# PCB_esp32.net
KiCad netlist of a schematic drawn in Altium Designer
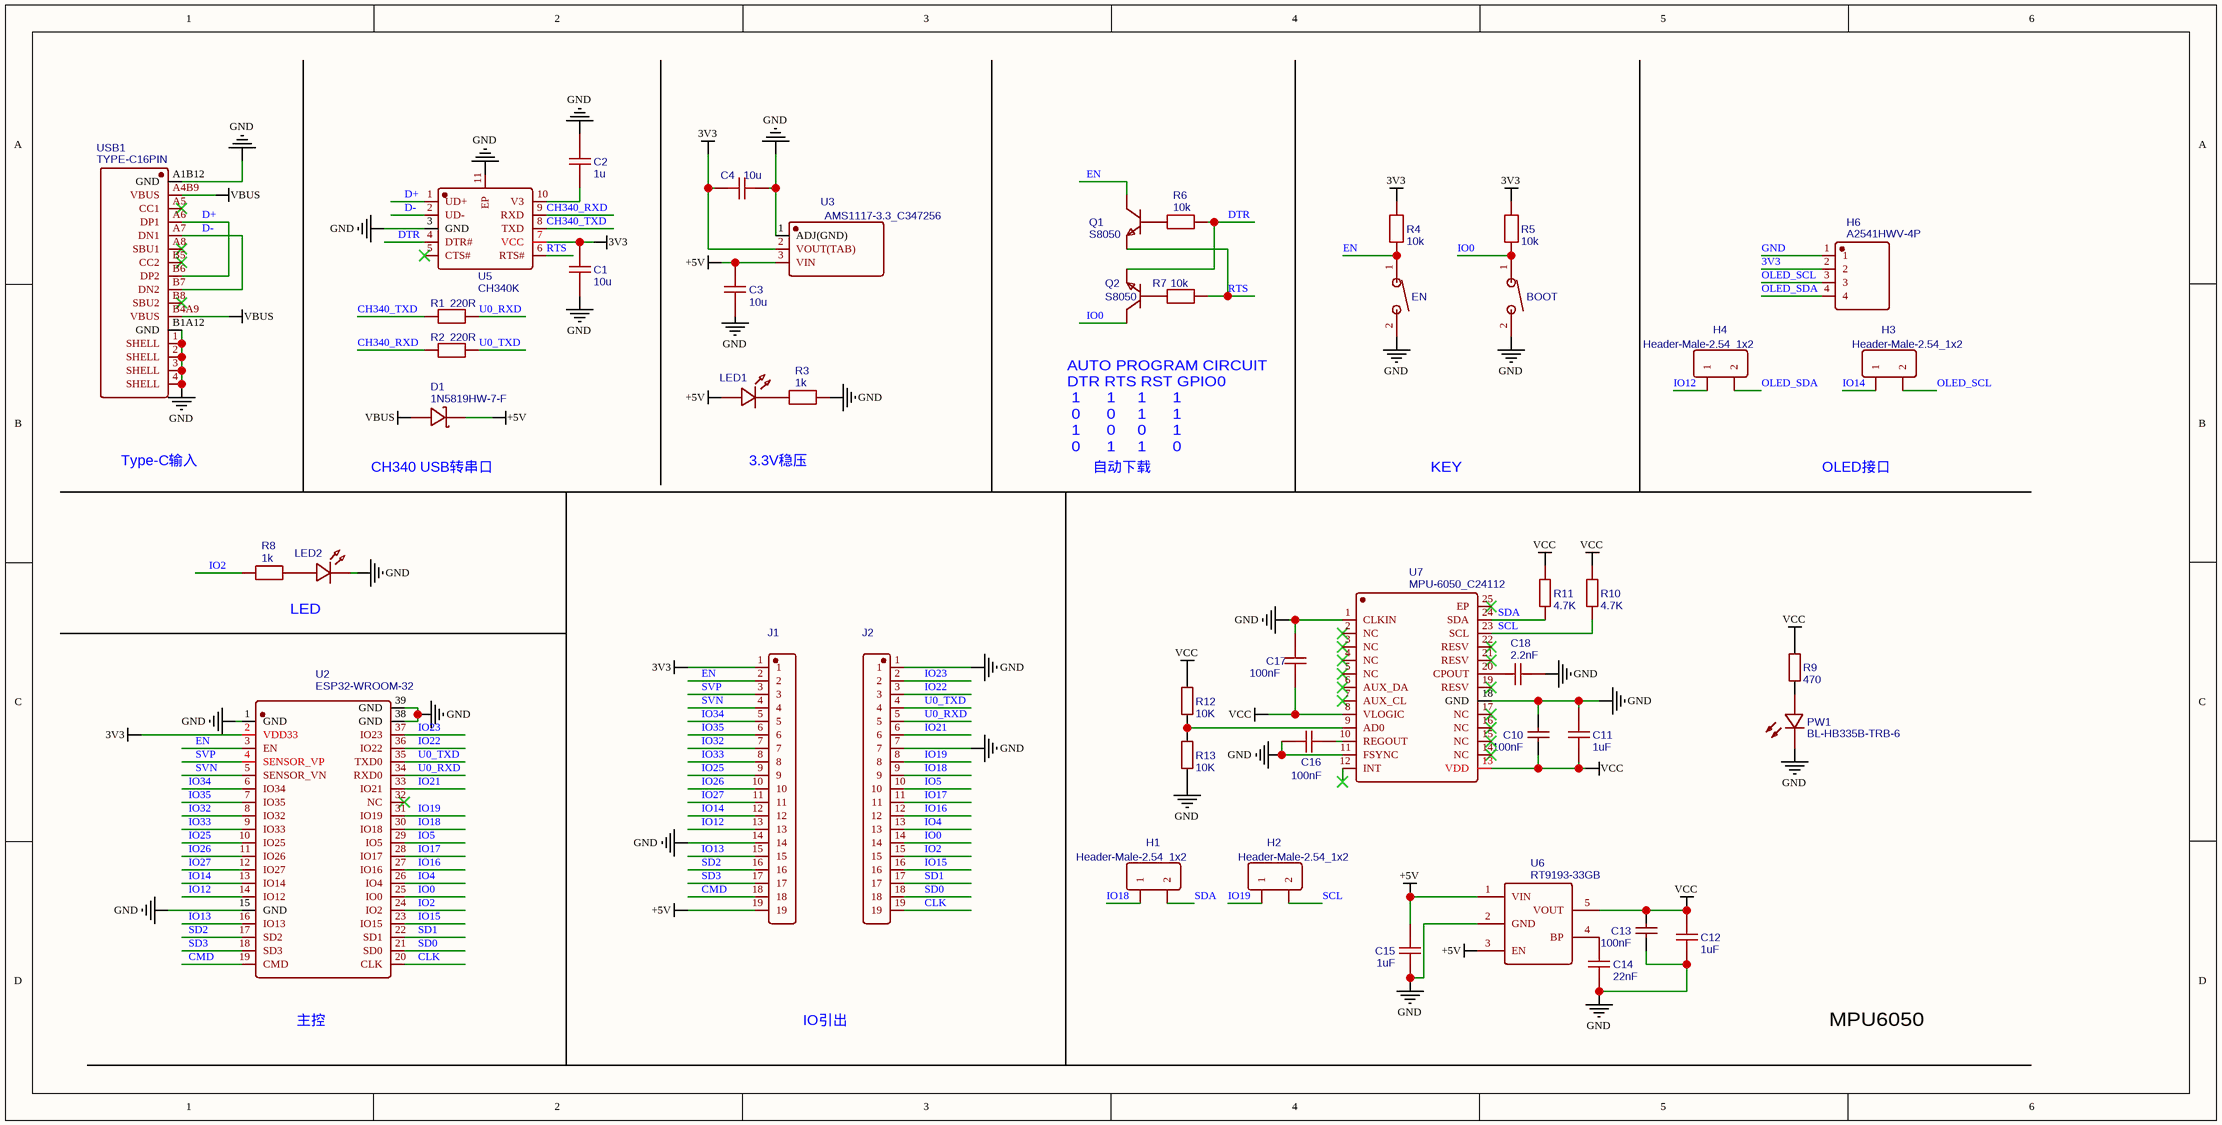
[diagram p0: PCB_esp32扩展板.schdoc]

(export (version "E")
  (design (tool "Eeschema 10.0.6"))
  (components
    (comp (ref "BOOT")
      (value "TSA343G00D-250J2")
      (fields (field (name "BOM_SUPPLIER PART") "C354947") (field (name "CONTRIBUTOR") "LCSC"))
      (libsource (lib "altium-import") (part "root_3_TSA343G00D-250J2_"))
    )
    (comp (ref "C1")
      (value "10u")
      (fields (field (name "CONTRIBUTOR") "LCEDA_Lib"))
      (libsource (lib "altium-import") (part "root_1_10u_"))
    )
    (comp (ref "C2")
      (value "1u")
      (fields (field (name "CONTRIBUTOR") "LCEDA_Lib"))
      (libsource (lib "altium-import") (part "root_1_1u_"))
    )
    (comp (ref "C3")
      (value "10u")
      (fields (field (name "CONTRIBUTOR") "LCEDA_Lib"))
      (libsource (lib "altium-import") (part "root_3_10u_"))
    )
    (comp (ref "C4")
      (value "10u")
      (fields (field (name "CONTRIBUTOR") "LCEDA_Lib"))
      (libsource (lib "altium-import") (part "root_0_10u_"))
    )
    (comp (ref "C10")
      (value "100nF")
      (fields
        (field (name "BOM_MANUFACTURER PART") "CT41G-0603-2X1-50V-0.1μF-K(N)")
        (field (name "BOM_SUPPLIER PART") "C125205")
        (field (name "CONTRIBUTOR") "LCSC")
      )
      (libsource (lib "") (part "root_1_100nF__1"))
    )
    (comp (ref "C11")
      (value "1uF")
      (fields
        (field (name "BOM_SUPPLIER PART") "C162200")
        (field (name "BOM_MANUFACTURER PART") "GRM185R61E105KA12D")
        (field (name "CONTRIBUTOR") "LCSC")
      )
      (libsource (lib "") (part "root_1_1uF__1"))
    )
    (comp (ref "C12")
      (value "1uF")
      (fields
        (field (name "BOM_SUPPLIER PART") "C162200")
        (field (name "BOM_MANUFACTURER PART") "GRM185R61E105KA12D")
        (field (name "CONTRIBUTOR") "LCSC")
      )
      (libsource (lib "") (part "root_1_1uF__1"))
    )
    (comp (ref "C13")
      (value "100nF")
      (fields
        (field (name "BOM_MANUFACTURER PART") "CT41G-0603-2X1-50V-0.1μF-K(N)")
        (field (name "BOM_SUPPLIER PART") "C125205")
        (field (name "CONTRIBUTOR") "LCSC")
      )
      (libsource (lib "") (part "root_1_100nF__1"))
    )
    (comp (ref "C14")
      (value "22nF")
      (fields
        (field (name "BOM_SUPPLIER PART") "C302021")
        (field (name "BOM_MANUFACTURER PART") "0603B223K500CT")
        (field (name "CONTRIBUTOR") "LCSC")
      )
      (libsource (lib "altium-import") (part "root_1_22nF_"))
    )
    (comp (ref "C15")
      (value "1uF")
      (fields
        (field (name "BOM_SUPPLIER PART") "C162200")
        (field (name "BOM_MANUFACTURER PART") "GRM185R61E105KA12D")
        (field (name "CONTRIBUTOR") "LCSC")
      )
      (libsource (lib "altium-import") (part "root_1_1uF_"))
    )
    (comp (ref "C16")
      (value "100nF")
      (fields
        (field (name "BOM_MANUFACTURER PART") "CC0603KRX7R9BB104")
        (field (name "BOM_SUPPLIER PART") "C14663")
      )
      (libsource (lib "altium-import") (part "root_2_100nF_"))
    )
    (comp (ref "C17")
      (value "100nF")
      (fields
        (field (name "BOM_MANUFACTURER PART") "CC0603KRX7R9BB104")
        (field (name "BOM_SUPPLIER PART") "C14663")
      )
      (libsource (lib "altium-import") (part "root_1_100nF_"))
    )
    (comp (ref "C18")
      (value "2.2nF")
      (fields
        (field (name "BOM_SUPPLIER PART") "C309517")
        (field (name "BOM_MANUFACTURER PART") "CS0603KRX7R9BB222")
        (field (name "CONTRIBUTOR") "LCSC")
      )
      (libsource (lib "altium-import") (part "root_1_2.2nF_"))
    )
    (comp (ref "D1")
      (value "1N5819HW-7-F")
      (fields (field (name "BOM_SUPPLIER PART") "C82544"))
      (libsource (lib "altium-import") (part "root_0_1N5819HW-7-F_"))
    )
    (comp (ref "EN")
      (value "TSA343G00D-250J2")
      (fields (field (name "BOM_SUPPLIER PART") "C354947") (field (name "CONTRIBUTOR") "LCSC"))
      (libsource (lib "altium-import") (part "root_3_TSA343G00D-250J2_"))
    )
    (comp (ref "H1")
      (value "Header-Male-2.54_1x2")
      (fields (field (name "BOM_MANUFACTURER PART") "826629-2") (field (name "BOM_SUPPLIER PART") "C86471"))
      (libsource (lib "altium-import") (part "root_1_Header-Male-2.54_1x2_"))
    )
    (comp (ref "H2")
      (value "Header-Male-2.54_1x2")
      (fields (field (name "BOM_MANUFACTURER PART") "826629-2") (field (name "BOM_SUPPLIER PART") "C86471"))
      (libsource (lib "altium-import") (part "root_1_Header-Male-2.54_1x2_"))
    )
    (comp (ref "H3")
      (value "Header-Male-2.54_1x2")
      (fields (field (name "BOM_MANUFACTURER PART") "826629-2") (field (name "BOM_SUPPLIER PART") "C86471"))
      (libsource (lib "altium-import") (part "root_1_Header-Male-2.54_1x2_"))
    )
    (comp (ref "H4")
      (value "Header-Male-2.54_1x2")
      (fields (field (name "BOM_MANUFACTURER PART") "826629-2") (field (name "BOM_SUPPLIER PART") "C86471"))
      (libsource (lib "altium-import") (part "root_1_Header-Male-2.54_1x2_"))
    )
    (comp (ref "H6")
      (value "A2541HWV-4P")
      (fields (field (name "BOM_SUPPLIER PART") "C225501") (field (name "CONTRIBUTOR") "LCSC"))
      (libsource (lib "altium-import") (part "root_0_A2541HWV-4P_"))
    )
    (comp (ref "J1")
      (value "Header-Male-2.54_1x19")
      (fields
        (field (name "BOM_MANUFACTURER PART") "2.54mm 1*20PHeader")
        (field (name "BOM_SUPPLIER PART") "C50981")
        (field (name "CONTRIBUTOR") "shiyindebcd")
      )
      (libsource (lib "") (part "root_0_Header-Male-2.54_1x19__1"))
    )
    (comp (ref "J2")
      (value "Header-Male-2.54_1x19")
      (fields
        (field (name "BOM_MANUFACTURER PART") "2.54mm 1*20PHeader")
        (field (name "BOM_SUPPLIER PART") "C50981")
        (field (name "CONTRIBUTOR") "shiyindebcd")
      )
      (libsource (lib "altium-import") (part "root_0_Header-Male-2.54_1x19_"))
    )
    (comp (ref "LED1")
      (value "LED-0603_R")
      (fields
        (field (name "BOM_MANUFACTURER PART") "19-217/R6C-AL1M2VY/3T")
        (field (name "BOM_SUPPLIER PART") "C72044")
        (field (name "CONTRIBUTOR") "LCEDA_01")
      )
      (libsource (lib "altium-import") (part "root_0_LED-0603_R_"))
    )
    (comp (ref "LED2")
      (value "LED-0603_R")
      (fields
        (field (name "BOM_MANUFACTURER PART") "19-217/R6C-AL1M2VY/3T")
        (field (name "BOM_SUPPLIER PART") "C72044")
        (field (name "CONTRIBUTOR") "LCEDA_01")
      )
      (libsource (lib "altium-import") (part "root_0_LED-0603_R_"))
    )
    (comp (ref "PW1")
      (value "BL-HB335B-TRB-6")
      (fields (field (name "BOM_SUPPLIER PART") "C189307") (field (name "CONTRIBUTOR") "LCSC"))
      (libsource (lib "altium-import") (part "root_1_BL-HB335B-TRB-6_"))
    )
    (comp (ref "Q1")
      (value "S8050")
      (fields (field (name "BOM_SUPPLIER PART") "C2688231") (field (name "CONTRIBUTOR") "LCSC"))
      (libsource (lib "altium-import") (part "root_0_S8050_"))
    )
    (comp (ref "Q2")
      (value "S8050")
      (fields (field (name "BOM_SUPPLIER PART") "C2688231") (field (name "CONTRIBUTOR") "LCSC"))
      (libsource (lib "altium-import") (part "root_2_S8050_"))
    )
    (comp (ref "R1")
      (value "220R")
      (fields (field (name "CONTRIBUTOR") "LCEDA_Lib"))
      (libsource (lib "altium-import") (part "root_0_220R_"))
    )
    (comp (ref "R2")
      (value "220R")
      (fields (field (name "CONTRIBUTOR") "LCEDA_Lib"))
      (libsource (lib "altium-import") (part "root_0_220R_"))
    )
    (comp (ref "R3")
      (value "1k")
      (fields (field (name "CONTRIBUTOR") "LCEDA_Lib"))
      (libsource (lib "altium-import") (part "root_0_1k_"))
    )
    (comp (ref "R4")
      (value "10k")
      (fields (field (name "CONTRIBUTOR") "LCEDA_Lib"))
      (libsource (lib "altium-import") (part "root_1_10k_"))
    )
    (comp (ref "R5")
      (value "10k")
      (fields (field (name "CONTRIBUTOR") "LCEDA_Lib"))
      (libsource (lib "altium-import") (part "root_1_10k_"))
    )
    (comp (ref "R6")
      (value "10k")
      (fields (field (name "CONTRIBUTOR") "LCEDA_Lib"))
      (libsource (lib "altium-import") (part "root_0_10k_"))
    )
    (comp (ref "R7")
      (value "10k")
      (fields (field (name "CONTRIBUTOR") "LCEDA_Lib"))
      (libsource (lib "altium-import") (part "root_0_10k_"))
    )
    (comp (ref "R8")
      (value "1k")
      (fields (field (name "CONTRIBUTOR") "LCEDA_Lib"))
      (libsource (lib "altium-import") (part "root_0_1k_"))
    )
    (comp (ref "R9")
      (value "470")
      (fields
        (field (name "BOM_MANUFACTURER PART") "CR0805J80471G")
        (field (name "BOM_SUPPLIER PART") "C102016")
      )
      (libsource (lib "altium-import") (part "root_1_470_"))
    )
    (comp (ref "R10")
      (value "4.7K")
      (fields
        (field (name "BOM_SUPPLIER PART") "C269746")
        (field (name "BOM_MANUFACTURER PART") "RMC08054.7K1%N")
        (field (name "CONTRIBUTOR") "LCSC")
      )
      (libsource (lib "altium-import") (part "root_1_4.7K_"))
    )
    (comp (ref "R11")
      (value "4.7K")
      (fields
        (field (name "BOM_SUPPLIER PART") "C269746")
        (field (name "BOM_MANUFACTURER PART") "RMC08054.7K1%N")
        (field (name "CONTRIBUTOR") "LCSC")
      )
      (libsource (lib "altium-import") (part "root_1_4.7K_"))
    )
    (comp (ref "R12")
      (value "10K")
      (fields
        (field (name "BOM_MANUFACTURER PART") "WR08X1002FTL")
        (field (name "BOM_SUPPLIER PART") "C108451")
      )
      (libsource (lib "altium-import") (part "root_3_10K_"))
    )
    (comp (ref "R13")
      (value "10K")
      (fields
        (field (name "BOM_MANUFACTURER PART") "WR08X1002FTL")
        (field (name "BOM_SUPPLIER PART") "C108451")
      )
      (libsource (lib "altium-import") (part "root_3_10K_"))
    )
    (comp (ref "U2")
      (value "ESP32-WROOM-32")
      (fields (field (name "BOM_SUPPLIER PART") "C503587") (field (name "CONTRIBUTOR") "LCSC"))
      (libsource (lib "altium-import") (part "root_0_ESP32-WROOM-32_"))
    )
    (comp (ref "U3")
      (value "AMS1117-3.3_C347256")
      (fields
        (field (name "BOM_SUPPLIER PART") "C347256")
        (field (name "BOM_MANUFACTURER PART") "AMS1117-3.3")
        (field (name "CONTRIBUTOR") "LCSC")
      )
      (libsource (lib "altium-import") (part "root_0_AMS1117-3.3_C347256_"))
    )
    (comp (ref "U5")
      (value "CH340K")
      (fields (field (name "BOM_SUPPLIER PART") "C968586") (field (name "CONTRIBUTOR") "LCSC"))
      (libsource (lib "altium-import") (part "root_0_CH340K_"))
    )
    (comp (ref "U6")
      (value "RT9193-33GB")
      (fields (field (name "BOM_SUPPLIER PART") "C15651"))
      (libsource (lib "altium-import") (part "root_0_RT9193-33GB_"))
    )
    (comp (ref "U7")
      (value "MPU-6050_C24112")
      (fields (field (name "BOM_MANUFACTURER PART") "MPU-6050") (field (name "BOM_SUPPLIER PART") "C24112"))
      (libsource (lib "altium-import") (part "root_0_MPU-6050_C24112_"))
    )
    (comp (ref "USB1")
      (value "TYPE-C16PIN")
      (fields (field (name "BOM_SUPPLIER PART") "C393939") (field (name "CONTRIBUTOR") "LCSC"))
      (libsource (lib "altium-import") (part "root_0_TYPE-C16PIN_"))
    )
  )
  (nets
    (net (code "1") (name "+5V") (class "Default")
      (node (ref "C15") (pin "1") (pinfunction "1_1") (pintype "passive"))
      (node (ref "C3") (pin "1") (pinfunction "1_1") (pintype "passive"))
      (node (ref "D1") (pin "2") (pinfunction "K_2") (pintype "passive"))
      (node (ref "J1") (pin "19") (pinfunction "19_19") (pintype "passive"))
      (node (ref "LED1") (pin "1") (pinfunction "1_1") (pintype "passive"))
      (node (ref "U3") (pin "3") (pinfunction "VIN_3") (pintype "passive"))
      (node (ref "U6") (pin "1") (pinfunction "VIN_1") (pintype "passive"))
      (node (ref "U6") (pin "3") (pinfunction "EN_3") (pintype "passive"))
    )
    (net (code "2") (name "/CH340_RXD") (class "Default")
      (node (ref "R2") (pin "1") (pinfunction "1_1") (pintype "passive"))
      (node (ref "U5") (pin "9") (pinfunction "RXD_9") (pintype "passive"))
    )
    (net (code "3") (name "/CH340_TXD") (class "Default")
      (node (ref "R1") (pin "1") (pinfunction "1_1") (pintype "passive"))
      (node (ref "U5") (pin "8") (pinfunction "TXD_8") (pintype "passive"))
    )
    (net (code "4") (name "/CLK") (class "Default")
      (node (ref "J2") (pin "19") (pinfunction "19_19") (pintype "passive"))
      (node (ref "U2") (pin "20") (pinfunction "CLK_20") (pintype "passive"))
    )
    (net (code "5") (name "/CMD") (class "Default")
      (node (ref "J1") (pin "18") (pinfunction "18_18") (pintype "passive"))
      (node (ref "U2") (pin "19") (pinfunction "CMD_19") (pintype "passive"))
    )
    (net (code "6") (name "/D+") (class "Default")
      (node (ref "U5") (pin "1") (pinfunction "UD+_1") (pintype "passive"))
      (node (ref "USB1") (pin "A6") (pinfunction "DP1_A6") (pintype "passive"))
      (node (ref "USB1") (pin "B6") (pinfunction "DP2_B6") (pintype "passive"))
    )
    (net (code "7") (name "/D-") (class "Default")
      (node (ref "U5") (pin "2") (pinfunction "UD-_2") (pintype "passive"))
      (node (ref "USB1") (pin "A7") (pinfunction "DN1_A7") (pintype "passive"))
      (node (ref "USB1") (pin "B7") (pinfunction "DN2_B7") (pintype "passive"))
    )
    (net (code "8") (name "/DTR") (class "Default")
      (node (ref "Q2") (pin "2") (pinfunction "E_2") (pintype "passive"))
      (node (ref "R6") (pin "2") (pinfunction "2_2") (pintype "passive"))
      (node (ref "U5") (pin "4") (pinfunction "DTR#_4") (pintype "passive"))
    )
    (net (code "9") (name "/EN") (class "Default")
      (node (ref "EN") (pin "1") (pinfunction "1_1") (pintype "passive"))
      (node (ref "J1") (pin "2") (pinfunction "2_2") (pintype "passive"))
      (node (ref "Q1") (pin "3") (pinfunction "C_3") (pintype "passive"))
      (node (ref "R4") (pin "1") (pinfunction "1_1") (pintype "passive"))
      (node (ref "U2") (pin "3") (pinfunction "EN_3") (pintype "passive"))
    )
    (net (code "10") (name "/IO0") (class "Default")
      (node (ref "BOOT") (pin "1") (pinfunction "1_1") (pintype "passive"))
      (node (ref "J2") (pin "14") (pinfunction "14_14") (pintype "passive"))
      (node (ref "Q2") (pin "3") (pinfunction "C_3") (pintype "passive"))
      (node (ref "R5") (pin "1") (pinfunction "1_1") (pintype "passive"))
      (node (ref "U2") (pin "25") (pinfunction "IO0_25") (pintype "passive"))
    )
    (net (code "11") (name "/IO2") (class "Default")
      (node (ref "J2") (pin "15") (pinfunction "15_15") (pintype "passive"))
      (node (ref "R8") (pin "1") (pinfunction "1_1") (pintype "passive"))
      (node (ref "U2") (pin "24") (pinfunction "IO2_24") (pintype "passive"))
    )
    (net (code "12") (name "/IO4") (class "Default")
      (node (ref "J2") (pin "13") (pinfunction "13_13") (pintype "passive"))
      (node (ref "U2") (pin "26") (pinfunction "IO4_26") (pintype "passive"))
    )
    (net (code "13") (name "/IO5") (class "Default")
      (node (ref "J2") (pin "10") (pinfunction "10_10") (pintype "passive"))
      (node (ref "U2") (pin "29") (pinfunction "IO5_29") (pintype "passive"))
    )
    (net (code "14") (name "/IO12") (class "Default")
      (node (ref "H4") (pin "1") (pinfunction "1_1") (pintype "passive"))
      (node (ref "J1") (pin "13") (pinfunction "13_13") (pintype "passive"))
      (node (ref "U2") (pin "14") (pinfunction "IO12_14") (pintype "passive"))
    )
    (net (code "15") (name "/IO13") (class "Default")
      (node (ref "J1") (pin "15") (pinfunction "15_15") (pintype "passive"))
      (node (ref "U2") (pin "16") (pinfunction "IO13_16") (pintype "passive"))
    )
    (net (code "16") (name "/IO14") (class "Default")
      (node (ref "H3") (pin "1") (pinfunction "1_1") (pintype "passive"))
      (node (ref "J1") (pin "12") (pinfunction "12_12") (pintype "passive"))
      (node (ref "U2") (pin "13") (pinfunction "IO14_13") (pintype "passive"))
    )
    (net (code "17") (name "/IO15") (class "Default")
      (node (ref "J2") (pin "16") (pinfunction "16_16") (pintype "passive"))
      (node (ref "U2") (pin "23") (pinfunction "IO15_23") (pintype "passive"))
    )
    (net (code "18") (name "/IO16") (class "Default")
      (node (ref "J2") (pin "12") (pinfunction "12_12") (pintype "passive"))
      (node (ref "U2") (pin "27") (pinfunction "IO16_27") (pintype "passive"))
    )
    (net (code "19") (name "/IO17") (class "Default")
      (node (ref "J2") (pin "11") (pinfunction "11_11") (pintype "passive"))
      (node (ref "U2") (pin "28") (pinfunction "IO17_28") (pintype "passive"))
    )
    (net (code "20") (name "/IO18") (class "Default")
      (node (ref "H1") (pin "1") (pinfunction "1_1") (pintype "passive"))
      (node (ref "J2") (pin "9") (pinfunction "9_9") (pintype "passive"))
      (node (ref "U2") (pin "30") (pinfunction "IO18_30") (pintype "passive"))
    )
    (net (code "21") (name "/IO19") (class "Default")
      (node (ref "H2") (pin "1") (pinfunction "1_1") (pintype "passive"))
      (node (ref "J2") (pin "8") (pinfunction "8_8") (pintype "passive"))
      (node (ref "U2") (pin "31") (pinfunction "IO19_31") (pintype "passive"))
    )
    (net (code "22") (name "/IO21") (class "Default")
      (node (ref "J2") (pin "6") (pinfunction "6_6") (pintype "passive"))
      (node (ref "U2") (pin "33") (pinfunction "IO21_33") (pintype "passive"))
    )
    (net (code "23") (name "/IO22") (class "Default")
      (node (ref "J2") (pin "3") (pinfunction "3_3") (pintype "passive"))
      (node (ref "U2") (pin "36") (pinfunction "IO22_36") (pintype "passive"))
    )
    (net (code "24") (name "/IO23") (class "Default")
      (node (ref "J2") (pin "2") (pinfunction "2_2") (pintype "passive"))
      (node (ref "U2") (pin "37") (pinfunction "IO23_37") (pintype "passive"))
    )
    (net (code "25") (name "/IO25") (class "Default")
      (node (ref "J1") (pin "9") (pinfunction "9_9") (pintype "passive"))
      (node (ref "U2") (pin "10") (pinfunction "IO25_10") (pintype "passive"))
    )
    (net (code "26") (name "/IO26") (class "Default")
      (node (ref "J1") (pin "10") (pinfunction "10_10") (pintype "passive"))
      (node (ref "U2") (pin "11") (pinfunction "IO26_11") (pintype "passive"))
    )
    (net (code "27") (name "/IO27") (class "Default")
      (node (ref "J1") (pin "11") (pinfunction "11_11") (pintype "passive"))
      (node (ref "U2") (pin "12") (pinfunction "IO27_12") (pintype "passive"))
    )
    (net (code "28") (name "/IO32") (class "Default")
      (node (ref "J1") (pin "7") (pinfunction "7_7") (pintype "passive"))
      (node (ref "U2") (pin "8") (pinfunction "IO32_8") (pintype "passive"))
    )
    (net (code "29") (name "/IO33") (class "Default")
      (node (ref "J1") (pin "8") (pinfunction "8_8") (pintype "passive"))
      (node (ref "U2") (pin "9") (pinfunction "IO33_9") (pintype "passive"))
    )
    (net (code "30") (name "/IO34") (class "Default")
      (node (ref "J1") (pin "5") (pinfunction "5_5") (pintype "passive"))
      (node (ref "U2") (pin "6") (pinfunction "IO34_6") (pintype "passive"))
    )
    (net (code "31") (name "/IO35") (class "Default")
      (node (ref "J1") (pin "6") (pinfunction "6_6") (pintype "passive"))
      (node (ref "U2") (pin "7") (pinfunction "IO35_7") (pintype "passive"))
    )
    (net (code "32") (name "/OLED_SCL") (class "Default")
      (node (ref "H3") (pin "2") (pinfunction "2_2") (pintype "passive"))
      (node (ref "H6") (pin "3") (pinfunction "3_3") (pintype "passive"))
    )
    (net (code "33") (name "/OLED_SDA") (class "Default")
      (node (ref "H4") (pin "2") (pinfunction "2_2") (pintype "passive"))
      (node (ref "H6") (pin "4") (pinfunction "4_4") (pintype "passive"))
    )
    (net (code "34") (name "/RTS") (class "Default")
      (node (ref "Q1") (pin "2") (pinfunction "E_2") (pintype "passive"))
      (node (ref "R7") (pin "2") (pinfunction "2_2") (pintype "passive"))
      (node (ref "U5") (pin "6") (pinfunction "RTS#_6") (pintype "passive"))
    )
    (net (code "35") (name "/SCL") (class "Default")
      (node (ref "H2") (pin "2") (pinfunction "2_2") (pintype "passive"))
      (node (ref "R10") (pin "1") (pinfunction "1_1") (pintype "passive"))
      (node (ref "U7") (pin "23") (pinfunction "SCL_23") (pintype "passive"))
    )
    (net (code "36") (name "/SD0") (class "Default")
      (node (ref "J2") (pin "18") (pinfunction "18_18") (pintype "passive"))
      (node (ref "U2") (pin "21") (pinfunction "SD0_21") (pintype "passive"))
    )
    (net (code "37") (name "/SD1") (class "Default")
      (node (ref "J2") (pin "17") (pinfunction "17_17") (pintype "passive"))
      (node (ref "U2") (pin "22") (pinfunction "SD1_22") (pintype "passive"))
    )
    (net (code "38") (name "/SD2") (class "Default")
      (node (ref "J1") (pin "16") (pinfunction "16_16") (pintype "passive"))
      (node (ref "U2") (pin "17") (pinfunction "SD2_17") (pintype "passive"))
    )
    (net (code "39") (name "/SD3") (class "Default")
      (node (ref "J1") (pin "17") (pinfunction "17_17") (pintype "passive"))
      (node (ref "U2") (pin "18") (pinfunction "SD3_18") (pintype "passive"))
    )
    (net (code "40") (name "/SDA") (class "Default")
      (node (ref "H1") (pin "2") (pinfunction "2_2") (pintype "passive"))
      (node (ref "R11") (pin "1") (pinfunction "1_1") (pintype "passive"))
      (node (ref "U7") (pin "24") (pinfunction "SDA_24") (pintype "passive"))
    )
    (net (code "41") (name "/SVN") (class "Default")
      (node (ref "J1") (pin "4") (pinfunction "4_4") (pintype "passive"))
      (node (ref "U2") (pin "5") (pinfunction "SENSOR_VN_5") (pintype "passive"))
    )
    (net (code "42") (name "/SVP") (class "Default")
      (node (ref "J1") (pin "3") (pinfunction "3_3") (pintype "passive"))
      (node (ref "U2") (pin "4") (pinfunction "SENSOR_VP_4") (pintype "passive"))
    )
    (net (code "43") (name "/U0_RXD") (class "Default")
      (node (ref "J2") (pin "5") (pinfunction "5_5") (pintype "passive"))
      (node (ref "R1") (pin "2") (pinfunction "2_2") (pintype "passive"))
      (node (ref "U2") (pin "34") (pinfunction "RXD0_34") (pintype "passive"))
    )
    (net (code "44") (name "/U0_TXD") (class "Default")
      (node (ref "J2") (pin "4") (pinfunction "4_4") (pintype "passive"))
      (node (ref "R2") (pin "2") (pinfunction "2_2") (pintype "passive"))
      (node (ref "U2") (pin "35") (pinfunction "TXD0_35") (pintype "passive"))
    )
    (net (code "45") (name "3V3") (class "Default")
      (node (ref "C1") (pin "2") (pinfunction "2_2") (pintype "passive"))
      (node (ref "C4") (pin "1") (pinfunction "1_1") (pintype "passive"))
      (node (ref "H6") (pin "2") (pinfunction "2_2") (pintype "passive"))
      (node (ref "J1") (pin "1") (pinfunction "1_1") (pintype "passive"))
      (node (ref "R4") (pin "2") (pinfunction "2_2") (pintype "passive"))
      (node (ref "R5") (pin "2") (pinfunction "2_2") (pintype "passive"))
      (node (ref "U2") (pin "2") (pinfunction "VDD33_2") (pintype "passive"))
      (node (ref "U3") (pin "2") (pinfunction "VOUT(TAB)_2") (pintype "passive"))
      (node (ref "U5") (pin "7") (pinfunction "VCC_7") (pintype "passive"))
    )
    (net (code "46") (name "GND") (class "Default")
      (node (ref "BOOT") (pin "2") (pinfunction "2_2") (pintype "passive"))
      (node (ref "C1") (pin "1") (pinfunction "1_1") (pintype "passive"))
      (node (ref "C10") (pin "2") (pinfunction "2_2") (pintype "passive"))
      (node (ref "C11") (pin "1") (pinfunction "1_1") (pintype "passive"))
      (node (ref "C12") (pin "2") (pinfunction "2_2") (pintype "passive"))
      (node (ref "C13") (pin "1") (pinfunction "1_1") (pintype "passive"))
      (node (ref "C14") (pin "2") (pinfunction "2_2") (pintype "passive"))
      (node (ref "C15") (pin "2") (pinfunction "2_2") (pintype "passive"))
      (node (ref "C16") (pin "2") (pinfunction "2_2") (pintype "passive"))
      (node (ref "C17") (pin "2") (pinfunction "2_2") (pintype "passive"))
      (node (ref "C18") (pin "1") (pinfunction "1_1") (pintype "passive"))
      (node (ref "C2") (pin "2") (pinfunction "2_2") (pintype "passive"))
      (node (ref "C3") (pin "2") (pinfunction "2_2") (pintype "passive"))
      (node (ref "C4") (pin "2") (pinfunction "2_2") (pintype "passive"))
      (node (ref "EN") (pin "2") (pinfunction "2_2") (pintype "passive"))
      (node (ref "H6") (pin "1") (pinfunction "1_1") (pintype "passive"))
      (node (ref "J1") (pin "14") (pinfunction "14_14") (pintype "passive"))
      (node (ref "J2") (pin "1") (pinfunction "1_1") (pintype "passive"))
      (node (ref "J2") (pin "7") (pinfunction "7_7") (pintype "passive"))
      (node (ref "LED2") (pin "2") (pinfunction "2_2") (pintype "passive"))
      (node (ref "PW1") (pin "1") (pinfunction "C_1") (pintype "passive"))
      (node (ref "R13") (pin "2") (pinfunction "2_2") (pintype "passive"))
      (node (ref "R3") (pin "2") (pinfunction "2_2") (pintype "passive"))
      (node (ref "U2") (pin "1") (pinfunction "GND_1") (pintype "passive"))
      (node (ref "U2") (pin "15") (pinfunction "GND_15") (pintype "passive"))
      (node (ref "U2") (pin "38") (pinfunction "GND_38") (pintype "passive"))
      (node (ref "U2") (pin "39") (pinfunction "GND_39") (pintype "passive"))
      (node (ref "U3") (pin "1") (pinfunction "ADJ(GND)_1") (pintype "passive"))
      (node (ref "U5") (pin "11") (pinfunction "EP_11") (pintype "passive"))
      (node (ref "U5") (pin "3") (pinfunction "GND_3") (pintype "passive"))
      (node (ref "U6") (pin "2") (pinfunction "GND_2") (pintype "passive"))
      (node (ref "U7") (pin "1") (pinfunction "CLKIN_1") (pintype "passive"))
      (node (ref "U7") (pin "11") (pinfunction "FSYNC_11") (pintype "passive"))
      (node (ref "U7") (pin "18") (pinfunction "GND_18") (pintype "passive"))
      (node (ref "USB1") (pin "1") (pinfunction "SHELL_1") (pintype "passive"))
      (node (ref "USB1") (pin "2") (pinfunction "SHELL_2") (pintype "passive"))
      (node (ref "USB1") (pin "3") (pinfunction "SHELL_3") (pintype "passive"))
      (node (ref "USB1") (pin "4") (pinfunction "SHELL_4") (pintype "passive"))
      (node (ref "USB1") (pin "A1B12") (pinfunction "GND_A1B12") (pintype "passive"))
      (node (ref "USB1") (pin "B1A12") (pinfunction "GND_B1A12") (pintype "passive"))
    )
    (net (code "47") (name "Net-(LED1-Pad2)") (class "Default")
      (node (ref "LED1") (pin "2") (pinfunction "2_2") (pintype "passive"))
      (node (ref "R3") (pin "1") (pinfunction "1_1") (pintype "passive"))
    )
    (net (code "48") (name "Net-(LED2-Pad1)") (class "Default")
      (node (ref "LED2") (pin "1") (pinfunction "1_1") (pintype "passive"))
      (node (ref "R8") (pin "2") (pinfunction "2_2") (pintype "passive"))
    )
    (net (code "49") (name "Net-(PW1-A)") (class "Default")
      (node (ref "PW1") (pin "2") (pinfunction "A_2") (pintype "passive"))
      (node (ref "R9") (pin "1") (pinfunction "1_1") (pintype "passive"))
    )
    (net (code "50") (name "Net-(Q1-B)") (class "Default")
      (node (ref "Q1") (pin "1") (pinfunction "B_1") (pintype "passive"))
      (node (ref "R6") (pin "1") (pinfunction "1_1") (pintype "passive"))
    )
    (net (code "51") (name "Net-(Q2-B)") (class "Default")
      (node (ref "Q2") (pin "1") (pinfunction "B_1") (pintype "passive"))
      (node (ref "R7") (pin "1") (pinfunction "1_1") (pintype "passive"))
    )
    (net (code "52") (name "Net-(U5-V3)") (class "Default")
      (node (ref "C2") (pin "1") (pinfunction "1_1") (pintype "passive"))
      (node (ref "U5") (pin "10") (pinfunction "V3_10") (pintype "passive"))
    )
    (net (code "53") (name "Net-(U6-BP)") (class "Default")
      (node (ref "C14") (pin "1") (pinfunction "1_1") (pintype "passive"))
      (node (ref "U6") (pin "4") (pinfunction "BP_4") (pintype "passive"))
    )
    (net (code "54") (name "Net-(U7-AD0)") (class "Default")
      (node (ref "R12") (pin "2") (pinfunction "2_2") (pintype "passive"))
      (node (ref "R13") (pin "1") (pinfunction "1_1") (pintype "passive"))
      (node (ref "U7") (pin "9") (pinfunction "AD0_9") (pintype "passive"))
    )
    (net (code "55") (name "Net-(U7-CPOUT)") (class "Default")
      (node (ref "C18") (pin "2") (pinfunction "2_2") (pintype "passive"))
      (node (ref "U7") (pin "20") (pinfunction "CPOUT_20") (pintype "passive"))
    )
    (net (code "56") (name "Net-(U7-REGOUT)") (class "Default")
      (node (ref "C16") (pin "1") (pinfunction "1_1") (pintype "passive"))
      (node (ref "U7") (pin "10") (pinfunction "REGOUT_10") (pintype "passive"))
    )
    (net (code "57") (name "VBUS") (class "Default")
      (node (ref "D1") (pin "1") (pinfunction "A_1") (pintype "passive"))
      (node (ref "USB1") (pin "A4B9") (pinfunction "VBUS_A4B9") (pintype "passive"))
      (node (ref "USB1") (pin "B4A9") (pinfunction "VBUS_B4A9") (pintype "passive"))
    )
    (net (code "58") (name "VCC") (class "Default")
      (node (ref "C10") (pin "1") (pinfunction "1_1") (pintype "passive"))
      (node (ref "C11") (pin "2") (pinfunction "2_2") (pintype "passive"))
      (node (ref "C12") (pin "1") (pinfunction "1_1") (pintype "passive"))
      (node (ref "C13") (pin "2") (pinfunction "2_2") (pintype "passive"))
      (node (ref "C17") (pin "1") (pinfunction "1_1") (pintype "passive"))
      (node (ref "R10") (pin "2") (pinfunction "2_2") (pintype "passive"))
      (node (ref "R11") (pin "2") (pinfunction "2_2") (pintype "passive"))
      (node (ref "R12") (pin "1") (pinfunction "1_1") (pintype "passive"))
      (node (ref "R9") (pin "2") (pinfunction "2_2") (pintype "passive"))
      (node (ref "U6") (pin "5") (pinfunction "VOUT_5") (pintype "passive"))
      (node (ref "U7") (pin "13") (pinfunction "VDD_13") (pintype "passive"))
      (node (ref "U7") (pin "8") (pinfunction "VLOGIC_8") (pintype "passive"))
    )
    (net (code "59") (name "unconnected-(U2-NC-Pad32)") (class "Default")
      (node (ref "U2") (pin "32") (pinfunction "NC_32") (pintype "passive+no_connect"))
    )
    (net (code "60") (name "unconnected-(U5-CTS#-Pad5)") (class "Default")
      (node (ref "U5") (pin "5") (pinfunction "CTS#_5") (pintype "passive+no_connect"))
    )
    (net (code "61") (name "unconnected-(U7-AUX_CL-Pad7)") (class "Default")
      (node (ref "U7") (pin "7") (pinfunction "AUX_CL_7") (pintype "passive+no_connect"))
    )
    (net (code "62") (name "unconnected-(U7-AUX_DA-Pad6)") (class "Default")
      (node (ref "U7") (pin "6") (pinfunction "AUX_DA_6") (pintype "passive+no_connect"))
    )
    (net (code "63") (name "unconnected-(U7-EP-Pad25)") (class "Default")
      (node (ref "U7") (pin "25") (pinfunction "EP_25") (pintype "passive+no_connect"))
    )
    (net (code "64") (name "unconnected-(U7-INT-Pad12)") (class "Default")
      (node (ref "U7") (pin "12") (pinfunction "INT_12") (pintype "passive+no_connect"))
    )
    (net (code "65") (name "unconnected-(U7-NC-Pad2)") (class "Default")
      (node (ref "U7") (pin "2") (pinfunction "NC_2") (pintype "passive+no_connect"))
    )
    (net (code "66") (name "unconnected-(U7-NC-Pad3)") (class "Default")
      (node (ref "U7") (pin "3") (pinfunction "NC_3") (pintype "passive+no_connect"))
    )
    (net (code "67") (name "unconnected-(U7-NC-Pad4)") (class "Default")
      (node (ref "U7") (pin "4") (pinfunction "NC_4") (pintype "passive+no_connect"))
    )
    (net (code "68") (name "unconnected-(U7-NC-Pad5)") (class "Default")
      (node (ref "U7") (pin "5") (pinfunction "NC_5") (pintype "passive+no_connect"))
    )
    (net (code "69") (name "unconnected-(U7-NC-Pad14)") (class "Default")
      (node (ref "U7") (pin "14") (pinfunction "NC_14") (pintype "passive+no_connect"))
    )
    (net (code "70") (name "unconnected-(U7-NC-Pad15)") (class "Default")
      (node (ref "U7") (pin "15") (pinfunction "NC_15") (pintype "passive+no_connect"))
    )
    (net (code "71") (name "unconnected-(U7-NC-Pad16)") (class "Default")
      (node (ref "U7") (pin "16") (pinfunction "NC_16") (pintype "passive+no_connect"))
    )
    (net (code "72") (name "unconnected-(U7-NC-Pad17)") (class "Default")
      (node (ref "U7") (pin "17") (pinfunction "NC_17") (pintype "passive+no_connect"))
    )
    (net (code "73") (name "unconnected-(U7-RESV-Pad19)") (class "Default")
      (node (ref "U7") (pin "19") (pinfunction "RESV_19") (pintype "passive+no_connect"))
    )
    (net (code "74") (name "unconnected-(U7-RESV-Pad21)") (class "Default")
      (node (ref "U7") (pin "21") (pinfunction "RESV_21") (pintype "passive+no_connect"))
    )
    (net (code "75") (name "unconnected-(U7-RESV-Pad22)") (class "Default")
      (node (ref "U7") (pin "22") (pinfunction "RESV_22") (pintype "passive+no_connect"))
    )
    (net (code "76") (name "unconnected-(USB1-CC1-PadA5)") (class "Default")
      (node (ref "USB1") (pin "A5") (pinfunction "CC1_A5") (pintype "passive+no_connect"))
    )
    (net (code "77") (name "unconnected-(USB1-CC2-PadB5)") (class "Default")
      (node (ref "USB1") (pin "B5") (pinfunction "CC2_B5") (pintype "passive+no_connect"))
    )
    (net (code "78") (name "unconnected-(USB1-SBU1-PadA8)") (class "Default")
      (node (ref "USB1") (pin "A8") (pinfunction "SBU1_A8") (pintype "passive+no_connect"))
    )
    (net (code "79") (name "unconnected-(USB1-SBU2-PadB8)") (class "Default")
      (node (ref "USB1") (pin "B8") (pinfunction "SBU2_B8") (pintype "passive+no_connect"))
    )
  )
)
